# Plant_Monitoring_System.net
KiCad netlist of a schematic drawn in Altium Designer
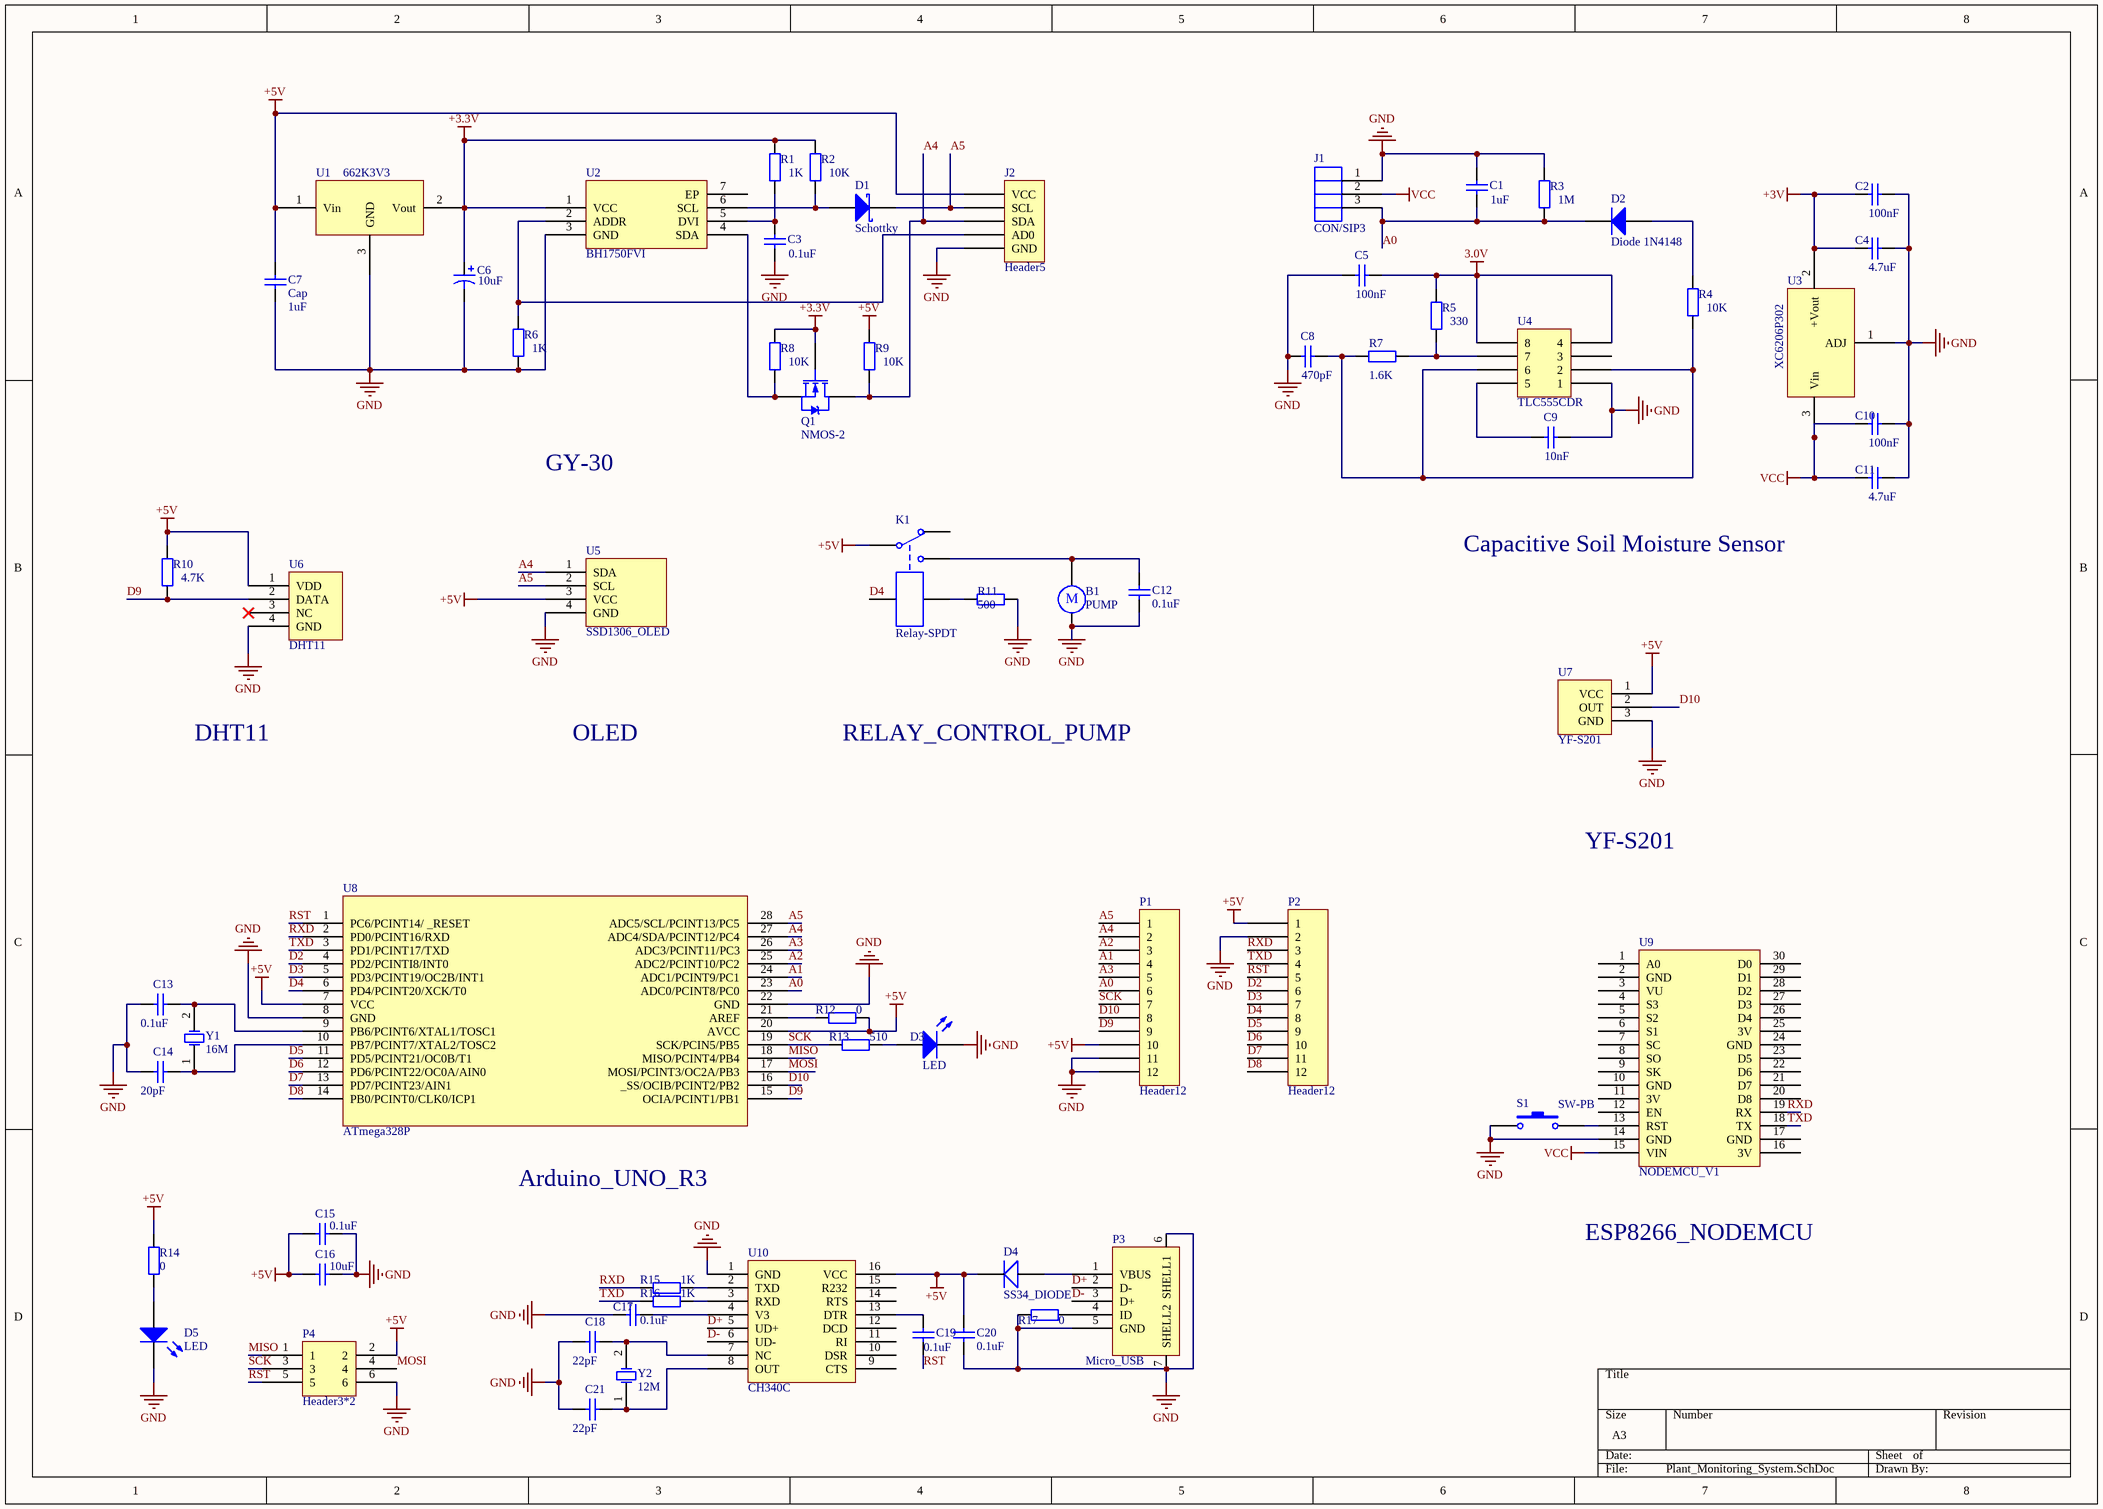
[diagram p0: Plant_Monitoring_System.SchDoc]

(export (version "E")
  (design (tool "Eeschema 10.0.6"))
  (components
    (comp (ref "B1")
      (value "PUMP")
      (footprint "RB5-10.5")
      (description "Motor, General Kind")
      (fields (field (name "PUBLISHER") "Altium Limited"))
      (libsource (lib "Miscellaneous Devices") (part "Motor"))
    )
    (comp (ref "C1")
      (value "1uF")
      (footprint "RAD-0.3")
      (description "Capacitor")
      (fields (field (name "PUBLISHER") "Altium Limited"))
      (libsource (lib "Miscellaneous Devices") (part "Cap"))
    )
    (comp (ref "C2")
      (value "100nF")
      (footprint "RAD-0.3")
      (description "Capacitor")
      (fields (field (name "PUBLISHER") "Altium Limited"))
      (libsource (lib "Miscellaneous Devices") (part "Cap"))
    )
    (comp (ref "C3")
      (value "0.1uF")
      (footprint "RAD-0.3")
      (description "Capacitor")
      (fields (field (name "PUBLISHER") "Altium Limited"))
      (libsource (lib "Miscellaneous Devices") (part "Cap"))
    )
    (comp (ref "C4")
      (value "4.7uF")
      (footprint "RAD-0.3")
      (description "Capacitor")
      (fields (field (name "PUBLISHER") "Altium Limited"))
      (libsource (lib "Miscellaneous Devices") (part "Cap"))
    )
    (comp (ref "C5")
      (value "100nF")
      (footprint "RAD-0.3")
      (description "Capacitor")
      (fields (field (name "PUBLISHER") "Altium Limited"))
      (libsource (lib "Miscellaneous Devices") (part "Cap"))
    )
    (comp (ref "C6")
      (value "10uF")
      (footprint "RB7.6-15")
      (description "Polarized Capacitor (Radial)")
      (fields (field (name "PUBLISHER") "Altium Limited"))
      (libsource (lib "Miscellaneous Devices") (part "Cap Pol1"))
    )
    (comp (ref "C7")
      (value "Cap")
      (footprint "RAD-0.3")
      (description "Capacitor")
      (fields (field (name "ALTIUM_VALUE") "1uF") (field (name "PUBLISHER") "Altium Limited"))
      (libsource (lib "Miscellaneous Devices") (part "Cap"))
    )
    (comp (ref "C8")
      (value "470pF")
      (footprint "RAD-0.3")
      (description "Capacitor")
      (fields (field (name "PUBLISHER") "Altium Limited"))
      (libsource (lib "Miscellaneous Devices") (part "Cap"))
    )
    (comp (ref "C9")
      (value "10nF")
      (footprint "RAD-0.3")
      (description "Capacitor")
      (fields (field (name "PUBLISHER") "Altium Limited"))
      (libsource (lib "Miscellaneous Devices") (part "Cap"))
    )
    (comp (ref "C10")
      (value "100nF")
      (footprint "RAD-0.3")
      (description "Capacitor")
      (fields (field (name "PUBLISHER") "Altium Limited"))
      (libsource (lib "Miscellaneous Devices") (part "Cap"))
    )
    (comp (ref "C11")
      (value "4.7uF")
      (footprint "RAD-0.3")
      (description "Capacitor")
      (fields (field (name "PUBLISHER") "Altium Limited"))
      (libsource (lib "Miscellaneous Devices") (part "Cap"))
    )
    (comp (ref "C12")
      (value "0.1uF")
      (footprint "RAD-0.3")
      (description "Capacitor")
      (fields (field (name "PUBLISHER") "Altium Limited"))
      (libsource (lib "Miscellaneous Devices") (part "Cap"))
    )
    (comp (ref "C13")
      (value "0.1uF")
      (footprint "RAD-0.3")
      (description "Capacitor")
      (fields (field (name "PUBLISHER") "Altium Limited"))
      (libsource (lib "Miscellaneous Devices") (part "Cap"))
    )
    (comp (ref "C14")
      (value "20pF")
      (footprint "RAD-0.3")
      (description "Capacitor")
      (fields (field (name "PUBLISHER") "Altium Limited"))
      (libsource (lib "Miscellaneous Devices") (part "Cap"))
    )
    (comp (ref "C15")
      (value "0.1uF")
      (footprint "RAD-0.3")
      (description "Capacitor")
      (fields (field (name "PUBLISHER") "Altium Limited"))
      (libsource (lib "Miscellaneous Devices") (part "Cap"))
    )
    (comp (ref "C16")
      (value "10uF")
      (footprint "RAD-0.3")
      (description "Capacitor")
      (fields (field (name "PUBLISHER") "Altium Limited"))
      (libsource (lib "Miscellaneous Devices") (part "Cap"))
    )
    (comp (ref "C17")
      (value "0.1uF")
      (footprint "RAD-0.3")
      (description "Capacitor")
      (fields (field (name "PUBLISHER") "Altium Limited"))
      (libsource (lib "Miscellaneous Devices") (part "Cap"))
    )
    (comp (ref "C18")
      (value "22pF")
      (footprint "RAD-0.3")
      (description "Capacitor")
      (fields (field (name "PUBLISHER") "Altium Limited"))
      (libsource (lib "Miscellaneous Devices") (part "Cap"))
    )
    (comp (ref "C19")
      (value "0.1uF")
      (footprint "RAD-0.3")
      (description "Capacitor")
      (fields (field (name "PUBLISHER") "Altium Limited"))
      (libsource (lib "Miscellaneous Devices") (part "Cap"))
    )
    (comp (ref "C20")
      (value "0.1uF")
      (footprint "RAD-0.3")
      (description "Capacitor")
      (fields (field (name "PUBLISHER") "Altium Limited"))
      (libsource (lib "Miscellaneous Devices") (part "Cap"))
    )
    (comp (ref "C21")
      (value "22pF")
      (footprint "RAD-0.3")
      (description "Capacitor")
      (fields (field (name "PUBLISHER") "Altium Limited"))
      (libsource (lib "Miscellaneous Devices") (part "Cap"))
    )
    (comp (ref "D1")
      (value "Schottky")
      (footprint "SMB")
      (description "Schottky Diode")
      (fields (field (name "PUBLISHER") "Altium Limited"))
      (libsource (lib "Miscellaneous Devices") (part "D Schottky"))
    )
    (comp (ref "D2")
      (value "Diode 1N4148")
      (footprint "DO-35")
      (description "High Conductance Fast Diode")
      (fields (field (name "PUBLISHER") "Altium Limited"))
      (libsource (lib "Miscellaneous Devices") (part "Diode 1N4148"))
    )
    (comp (ref "D3")
      (value "LED")
      (footprint "3.5X2.8X1.9")
      (description "Typical BLUE SiC LED")
      (fields (field (name "PUBLISHER") "Altium Limited"))
      (libsource (lib "Miscellaneous Devices") (part "LED3"))
    )
    (comp (ref "D4") (value "SS34_DIODE") (libsource (lib "Arduino") (part "SS34_DIODE")))
    (comp (ref "D5")
      (value "LED")
      (footprint "3.5X2.8X1.9")
      (description "Typical BLUE SiC LED")
      (fields (field (name "PUBLISHER") "Altium Limited"))
      (libsource (lib "Miscellaneous Devices") (part "LED3"))
    )
    (comp (ref "J1") (value "CON/SIP3") (libsource (lib "SOILHUMIDITY") (part "CON/SIP3")))
    (comp (ref "J2") (value "Header5") (libsource (lib "GY-30") (part "Header5")))
    (comp (ref "K1")
      (value "Relay-SPDT")
      (footprint "MODULE5B")
      (description "Single-Pole Dual-Throw Relay")
      (fields (field (name "PUBLISHER") "Altium Limited"))
      (libsource (lib "Miscellaneous Devices") (part "Relay-SPDT"))
    )
    (comp (ref "P1") (value "Header12") (libsource (lib "Arduino") (part "Header12")))
    (comp (ref "P2") (value "Header12") (libsource (lib "Arduino") (part "Header12")))
    (comp (ref "P3") (value "Micro_USB") (libsource (lib "Arduino") (part "Micro_USB")))
    (comp (ref "P4") (value "Header3*2") (libsource (lib "Arduino") (part "Header3*2")))
    (comp (ref "Q1")
      (value "NMOS-2")
      (footprint "TO-220AB")
      (description "N-Channel Power MOSFET")
      (fields (field (name "PUBLISHER") "Altium Limited"))
      (libsource (lib "Miscellaneous Devices") (part "NMOS-2"))
    )
    (comp (ref "R1")
      (value "1K")
      (footprint "AXIAL-0.4")
      (description "Resistor")
      (fields (field (name "PUBLISHER") "Altium Limited"))
      (libsource (lib "") (part "Res2_1"))
    )
    (comp (ref "R2")
      (value "10K")
      (footprint "AXIAL-0.4")
      (description "Resistor")
      (fields (field (name "PUBLISHER") "Altium Limited"))
      (libsource (lib "") (part "Res2_1"))
    )
    (comp (ref "R3")
      (value "1M")
      (footprint "AXIAL-0.4")
      (description "Resistor")
      (fields (field (name "PUBLISHER") "Altium Limited"))
      (libsource (lib "") (part "Res2_1"))
    )
    (comp (ref "R4")
      (value "10K")
      (footprint "AXIAL-0.4")
      (description "Resistor")
      (fields (field (name "PUBLISHER") "Altium Limited"))
      (libsource (lib "") (part "Res2_1"))
    )
    (comp (ref "R5")
      (value "330")
      (footprint "AXIAL-0.4")
      (description "Resistor")
      (fields (field (name "PUBLISHER") "Altium Limited"))
      (libsource (lib "") (part "Res2_1"))
    )
    (comp (ref "R6")
      (value "1K")
      (footprint "AXIAL-0.4")
      (description "Resistor")
      (fields (field (name "PUBLISHER") "Altium Limited"))
      (libsource (lib "") (part "Res2_1"))
    )
    (comp (ref "R7")
      (value "1.6K")
      (footprint "AXIAL-0.4")
      (description "Resistor")
      (fields (field (name "PUBLISHER") "Altium Limited"))
      (libsource (lib "Miscellaneous Devices") (part "Res2"))
    )
    (comp (ref "R8")
      (value "10K")
      (footprint "AXIAL-0.4")
      (description "Resistor")
      (fields (field (name "PUBLISHER") "Altium Limited"))
      (libsource (lib "") (part "Res2_1"))
    )
    (comp (ref "R9")
      (value "10K")
      (footprint "AXIAL-0.4")
      (description "Resistor")
      (fields (field (name "PUBLISHER") "Altium Limited"))
      (libsource (lib "") (part "Res2_1"))
    )
    (comp (ref "R10")
      (value "4.7K")
      (footprint "AXIAL-0.4")
      (description "Resistor")
      (fields (field (name "PUBLISHER") "Altium Limited"))
      (libsource (lib "") (part "Res2_1"))
    )
    (comp (ref "R11")
      (value "500")
      (footprint "AXIAL-0.4")
      (description "Resistor")
      (fields (field (name "PUBLISHER") "Altium Limited"))
      (libsource (lib "Miscellaneous Devices") (part "Res2"))
    )
    (comp (ref "R12")
      (value "0")
      (footprint "AXIAL-0.4")
      (description "Resistor")
      (fields (field (name "PUBLISHER") "Altium Limited"))
      (libsource (lib "Miscellaneous Devices") (part "Res2"))
    )
    (comp (ref "R13")
      (value "510")
      (footprint "AXIAL-0.4")
      (description "Resistor")
      (fields (field (name "PUBLISHER") "Altium Limited"))
      (libsource (lib "Miscellaneous Devices") (part "Res2"))
    )
    (comp (ref "R14")
      (value "0")
      (footprint "AXIAL-0.4")
      (description "Resistor")
      (fields (field (name "PUBLISHER") "Altium Limited"))
      (libsource (lib "") (part "Res2_2"))
    )
    (comp (ref "R15")
      (value "1K")
      (footprint "AXIAL-0.4")
      (description "Resistor")
      (fields (field (name "PUBLISHER") "Altium Limited"))
      (libsource (lib "Miscellaneous Devices") (part "Res2"))
    )
    (comp (ref "R16")
      (value "1K")
      (footprint "AXIAL-0.4")
      (description "Resistor")
      (fields (field (name "PUBLISHER") "Altium Limited"))
      (libsource (lib "Miscellaneous Devices") (part "Res2"))
    )
    (comp (ref "R17")
      (value "0")
      (footprint "AXIAL-0.4")
      (description "Resistor")
      (fields (field (name "PUBLISHER") "Altium Limited"))
      (libsource (lib "Miscellaneous Devices") (part "Res2"))
    )
    (comp (ref "S1")
      (value "SW-PB")
      (footprint "SPST-2")
      (description "Switch")
      (fields (field (name "PUBLISHER") "Altium Limited"))
      (libsource (lib "Miscellaneous Devices") (part "SW-PB"))
    )
    (comp (ref "U1") (value "662K3V3") (libsource (lib "GY-30") (part "662K3V3")))
    (comp (ref "U2") (value "BH1750FVI") (libsource (lib "GY-30") (part "BH1750FVI")))
    (comp (ref "U3") (value "XC6206P302") (libsource (lib "SOILHUMIDITY") (part "XC6206P302")))
    (comp (ref "U4") (value "TLC555CDR") (libsource (lib "SOILHUMIDITY") (part "TLC555CDR")))
    (comp (ref "U5") (value "SSD1306_OLED") (libsource (lib "OLEDIIC128X64") (part "SSD1306_OLED")))
    (comp (ref "U6") (value "DHT11") (libsource (lib "DHT11") (part "DHT11")))
    (comp (ref "U7") (value "YF-S201") (libsource (lib "YF-S201") (part "YF-S201")))
    (comp (ref "U8") (value "ATmega328P") (libsource (lib "Arduino") (part "ATmega328P")))
    (comp (ref "U9") (value "NODEMCU_V1") (libsource (lib "ESP8266") (part "NODEMCU_V1")))
    (comp (ref "U10") (value "CH340C") (libsource (lib "Arduino") (part "CH340C")))
    (comp (ref "Y1")
      (value "16M")
      (footprint "R38")
      (description "Crystal Oscillator")
      (fields (field (name "PUBLISHER") "Altium Limited"))
      (libsource (lib "Miscellaneous Devices") (part "XTAL"))
    )
    (comp (ref "Y2")
      (value "12M")
      (footprint "R38")
      (description "Crystal Oscillator")
      (fields (field (name "PUBLISHER") "Altium Limited"))
      (libsource (lib "Miscellaneous Devices") (part "XTAL"))
    )
  )
  (nets
    (net (code "1") (name "+3.3V") (class "Default")
      (node (ref "C6") (pin "1") (pinfunction "1_1") (pintype "passive"))
      (node (ref "Q1") (pin "1") (pinfunction "G_1") (pintype "passive"))
      (node (ref "R1") (pin "2") (pinfunction "2_2") (pintype "passive"))
      (node (ref "R2") (pin "2") (pinfunction "2_2") (pintype "passive"))
      (node (ref "R8") (pin "2") (pinfunction "2_2") (pintype "passive"))
      (node (ref "U1") (pin "2") (pinfunction "Vout_2") (pintype "passive"))
      (node (ref "U2") (pin "1") (pinfunction "VCC_1") (pintype "passive"))
    )
    (net (code "2") (name "+3V") (class "Default")
      (node (ref "C2") (pin "1") (pinfunction "1_1") (pintype "passive"))
      (node (ref "C4") (pin "1") (pinfunction "1_1") (pintype "passive"))
      (node (ref "U3") (pin "2") (pinfunction "+Vout_2") (pintype "passive"))
    )
    (net (code "3") (name "+5V") (class "Default")
      (node (ref "C15") (pin "1") (pinfunction "1_1") (pintype "passive"))
      (node (ref "C16") (pin "2") (pinfunction "2_2") (pintype "passive"))
      (node (ref "C20") (pin "1") (pinfunction "1_1") (pintype "passive"))
      (node (ref "C7") (pin "2") (pinfunction "2_2") (pintype "passive"))
      (node (ref "J2") (pin "1") (pinfunction "VCC_1") (pintype "passive"))
      (node (ref "K1") (pin "1") (pinfunction "1_1") (pintype "passive"))
      (node (ref "P1") (pin "10") (pinfunction "10_10") (pintype "passive"))
      (node (ref "P2") (pin "1") (pinfunction "1_1") (pintype "passive"))
      (node (ref "P4") (pin "2") (pinfunction "2_2") (pintype "passive"))
      (node (ref "R10") (pin "2") (pinfunction "2_2") (pintype "passive"))
      (node (ref "R12") (pin "2") (pinfunction "2_2") (pintype "passive"))
      (node (ref "R14") (pin "1") (pinfunction "1_1") (pintype "passive"))
      (node (ref "R9") (pin "2") (pinfunction "2_2") (pintype "passive"))
      (node (ref "U1") (pin "1") (pinfunction "Vin_1") (pintype "passive"))
      (node (ref "U10") (pin "16") (pinfunction "VCC_16") (pintype "passive"))
      (node (ref "U5") (pin "3") (pinfunction "VCC_3") (pintype "passive"))
      (node (ref "U6") (pin "1") (pinfunction "VDD_1") (pintype "passive"))
      (node (ref "U7") (pin "1") (pinfunction "VCC_1") (pintype "passive"))
      (node (ref "U8") (pin "20") (pinfunction "AVCC_20") (pintype "passive"))
      (node (ref "U8") (pin "7") (pinfunction "VCC_7") (pintype "passive"))
    )
    (net (code "4") (name "/A0") (class "Default")
      (node (ref "C1") (pin "1") (pinfunction "1_1") (pintype "passive"))
      (node (ref "D2") (pin "2") (pinfunction "K_2") (pintype "passive"))
      (node (ref "J1") (pin "3") (pinfunction "3_3") (pintype "passive"))
      (node (ref "P1") (pin "6") (pinfunction "6_6") (pintype "passive"))
      (node (ref "R3") (pin "1") (pinfunction "1_1") (pintype "passive"))
      (node (ref "U8") (pin "23") (pinfunction "ADC0/PCINT8/PC0_23") (pintype "passive"))
    )
    (net (code "5") (name "/A1") (class "Default")
      (node (ref "P1") (pin "4") (pinfunction "4_4") (pintype "passive"))
      (node (ref "U8") (pin "24") (pinfunction "ADC1/PCINT9/PC1_24") (pintype "passive"))
    )
    (net (code "6") (name "/A2") (class "Default")
      (node (ref "P1") (pin "3") (pinfunction "3_3") (pintype "passive"))
      (node (ref "U8") (pin "25") (pinfunction "ADC2/PCINT10/PC2_25") (pintype "passive"))
    )
    (net (code "7") (name "/A3") (class "Default")
      (node (ref "P1") (pin "5") (pinfunction "5_5") (pintype "passive"))
      (node (ref "U8") (pin "26") (pinfunction "ADC3/PCINT11/PC3_26") (pintype "passive"))
    )
    (net (code "8") (name "/A4") (class "Default")
      (node (ref "J2") (pin "3") (pinfunction "SDA_3") (pintype "passive"))
      (node (ref "P1") (pin "2") (pinfunction "2_2") (pintype "passive"))
      (node (ref "Q1") (pin "2") (pinfunction "D_2") (pintype "passive"))
      (node (ref "R9") (pin "1") (pinfunction "1_1") (pintype "passive"))
      (node (ref "U5") (pin "1") (pinfunction "SDA_1") (pintype "passive"))
      (node (ref "U8") (pin "27") (pinfunction "ADC4/SDA/PCINT12/PC4_27") (pintype "passive"))
    )
    (net (code "9") (name "/A5") (class "Default")
      (node (ref "D1") (pin "2") (pinfunction "K_2") (pintype "passive"))
      (node (ref "J2") (pin "2") (pinfunction "SCL_2") (pintype "passive"))
      (node (ref "P1") (pin "1") (pinfunction "1_1") (pintype "passive"))
      (node (ref "U5") (pin "2") (pinfunction "SCL_2") (pintype "passive"))
      (node (ref "U8") (pin "28") (pinfunction "ADC5/SCL/PCINT13/PC5_28") (pintype "passive"))
    )
    (net (code "10") (name "/D+") (class "Default")
      (node (ref "P3") (pin "2") (pinfunction "D-_2") (pintype "passive"))
      (node (ref "U10") (pin "5") (pinfunction "UD+_5") (pintype "passive"))
    )
    (net (code "11") (name "/D-") (class "Default")
      (node (ref "P3") (pin "3") (pinfunction "D+_3") (pintype "passive"))
      (node (ref "U10") (pin "6") (pinfunction "UD-_6") (pintype "passive"))
    )
    (net (code "12") (name "/D2") (class "Default")
      (node (ref "P2") (pin "6") (pinfunction "6_6") (pintype "passive"))
      (node (ref "U8") (pin "4") (pinfunction "PD2/PCINTI8/INT0_4") (pintype "passive"))
    )
    (net (code "13") (name "/D3") (class "Default")
      (node (ref "P2") (pin "7") (pinfunction "7_7") (pintype "passive"))
      (node (ref "U8") (pin "5") (pinfunction "PD3/PCINT19/OC2B/INT1_5") (pintype "passive"))
    )
    (net (code "14") (name "/D4") (class "Default")
      (node (ref "K1") (pin "4") (pinfunction "4_4") (pintype "passive"))
      (node (ref "P2") (pin "8") (pinfunction "8_8") (pintype "passive"))
      (node (ref "U8") (pin "6") (pinfunction "PD4/PCINT20/XCK/T0_6") (pintype "passive"))
    )
    (net (code "15") (name "/D5") (class "Default")
      (node (ref "P2") (pin "9") (pinfunction "9_9") (pintype "passive"))
      (node (ref "U8") (pin "11") (pinfunction "PD5/PCINT21/OC0B/T1_11") (pintype "passive"))
    )
    (net (code "16") (name "/D6") (class "Default")
      (node (ref "P2") (pin "10") (pinfunction "10_10") (pintype "passive"))
      (node (ref "U8") (pin "12") (pinfunction "PD6/PCINT22/OC0A/AIN0_12") (pintype "passive"))
    )
    (net (code "17") (name "/D7") (class "Default")
      (node (ref "P2") (pin "11") (pinfunction "11_11") (pintype "passive"))
      (node (ref "U8") (pin "13") (pinfunction "PD7/PCINT23/AIN1_13") (pintype "passive"))
    )
    (net (code "18") (name "/D8") (class "Default")
      (node (ref "P2") (pin "12") (pinfunction "12_12") (pintype "passive"))
      (node (ref "U8") (pin "14") (pinfunction "PB0/PCINT0/CLK0/ICP1_14") (pintype "passive"))
    )
    (net (code "19") (name "/D9") (class "Default")
      (node (ref "P1") (pin "9") (pinfunction "9_9") (pintype "passive"))
      (node (ref "R10") (pin "1") (pinfunction "1_1") (pintype "passive"))
      (node (ref "U6") (pin "2") (pinfunction "DATA_2") (pintype "passive"))
      (node (ref "U8") (pin "15") (pinfunction "OCIA/PCINT1/PB1_15") (pintype "passive"))
    )
    (net (code "20") (name "/D10") (class "Default")
      (node (ref "P1") (pin "8") (pinfunction "8_8") (pintype "passive"))
      (node (ref "U7") (pin "2") (pinfunction "OUT_2") (pintype "passive"))
      (node (ref "U8") (pin "16") (pinfunction "_SS/OCIB/PCINT2/PB2_16") (pintype "passive"))
    )
    (net (code "21") (name "/MISO") (class "Default")
      (node (ref "P4") (pin "1") (pinfunction "1_1") (pintype "passive"))
      (node (ref "U8") (pin "18") (pinfunction "MISO/PCINT4/PB4_18") (pintype "passive"))
    )
    (net (code "22") (name "/MOSI") (class "Default")
      (node (ref "P4") (pin "4") (pinfunction "4_4") (pintype "passive"))
      (node (ref "U8") (pin "17") (pinfunction "MOSI/PCINT3/OC2A/PB3_17") (pintype "passive"))
    )
    (net (code "23") (name "/RST") (class "Default")
      (node (ref "C19") (pin "1") (pinfunction "1_1") (pintype "passive"))
      (node (ref "P2") (pin "5") (pinfunction "5_5") (pintype "passive"))
      (node (ref "P4") (pin "5") (pinfunction "5_5") (pintype "passive"))
      (node (ref "U8") (pin "1") (pinfunction "PC6/PCINT14/__RESET_1") (pintype "passive"))
    )
    (net (code "24") (name "/RXD") (class "Default")
      (node (ref "P2") (pin "3") (pinfunction "3_3") (pintype "passive"))
      (node (ref "R15") (pin "1") (pinfunction "1_1") (pintype "passive"))
      (node (ref "U8") (pin "2") (pinfunction "PD0/PCINT16/RXD_2") (pintype "passive"))
      (node (ref "U9") (pin "19") (pinfunction "RX_19") (pintype "passive"))
    )
    (net (code "25") (name "/SCK") (class "Default")
      (node (ref "P1") (pin "7") (pinfunction "7_7") (pintype "passive"))
      (node (ref "P4") (pin "3") (pinfunction "3_3") (pintype "passive"))
      (node (ref "R13") (pin "1") (pinfunction "1_1") (pintype "passive"))
      (node (ref "U8") (pin "19") (pinfunction "SCK/PCIN5/PB5_19") (pintype "passive"))
    )
    (net (code "26") (name "/TXD") (class "Default")
      (node (ref "P2") (pin "4") (pinfunction "4_4") (pintype "passive"))
      (node (ref "R16") (pin "1") (pinfunction "1_1") (pintype "passive"))
      (node (ref "U8") (pin "3") (pinfunction "PD1/PCINT17/TXD_3") (pintype "passive"))
      (node (ref "U9") (pin "18") (pinfunction "TX_18") (pintype "passive"))
    )
    (net (code "27") (name "3.0V") (class "Default")
      (node (ref "C5") (pin "2") (pinfunction "2_2") (pintype "passive"))
      (node (ref "R5") (pin "2") (pinfunction "2_2") (pintype "passive"))
      (node (ref "U4") (pin "4") (pinfunction "4_4") (pintype "passive"))
      (node (ref "U4") (pin "8") (pinfunction "8_8") (pintype "passive"))
    )
    (net (code "28") (name "GND") (class "Default")
      (node (ref "B1") (pin "2") (pinfunction "2_2") (pintype "passive"))
      (node (ref "C1") (pin "2") (pinfunction "2_2") (pintype "passive"))
      (node (ref "C10") (pin "2") (pinfunction "2_2") (pintype "passive"))
      (node (ref "C11") (pin "2") (pinfunction "2_2") (pintype "passive"))
      (node (ref "C12") (pin "2") (pinfunction "2_2") (pintype "passive"))
      (node (ref "C13") (pin "2") (pinfunction "2_2") (pintype "passive"))
      (node (ref "C14") (pin "2") (pinfunction "2_2") (pintype "passive"))
      (node (ref "C15") (pin "2") (pinfunction "2_2") (pintype "passive"))
      (node (ref "C16") (pin "1") (pinfunction "1_1") (pintype "passive"))
      (node (ref "C17") (pin "2") (pinfunction "2_2") (pintype "passive"))
      (node (ref "C18") (pin "2") (pinfunction "2_2") (pintype "passive"))
      (node (ref "C2") (pin "2") (pinfunction "2_2") (pintype "passive"))
      (node (ref "C20") (pin "2") (pinfunction "2_2") (pintype "passive"))
      (node (ref "C21") (pin "2") (pinfunction "2_2") (pintype "passive"))
      (node (ref "C3") (pin "1") (pinfunction "1_1") (pintype "passive"))
      (node (ref "C4") (pin "2") (pinfunction "2_2") (pintype "passive"))
      (node (ref "C5") (pin "1") (pinfunction "1_1") (pintype "passive"))
      (node (ref "C6") (pin "2") (pinfunction "2_2") (pintype "passive"))
      (node (ref "C7") (pin "1") (pinfunction "1_1") (pintype "passive"))
      (node (ref "C8") (pin "1") (pinfunction "1_1") (pintype "passive"))
      (node (ref "C9") (pin "2") (pinfunction "2_2") (pintype "passive"))
      (node (ref "D3") (pin "2") (pinfunction "K_2") (pintype "passive"))
      (node (ref "D5") (pin "2") (pinfunction "K_2") (pintype "passive"))
      (node (ref "J1") (pin "1") (pinfunction "1_1") (pintype "passive"))
      (node (ref "J2") (pin "5") (pinfunction "GND_5") (pintype "passive"))
      (node (ref "P1") (pin "11") (pinfunction "11_11") (pintype "passive"))
      (node (ref "P1") (pin "12") (pinfunction "12_12") (pintype "passive"))
      (node (ref "P2") (pin "2") (pinfunction "2_2") (pintype "passive"))
      (node (ref "P3") (pin "5") (pinfunction "GND_5") (pintype "passive"))
      (node (ref "P3") (pin "6") (pinfunction "SHELL1_6") (pintype "passive"))
      (node (ref "P3") (pin "7") (pinfunction "SHELL2_7") (pintype "passive"))
      (node (ref "P4") (pin "6") (pinfunction "6_6") (pintype "passive"))
      (node (ref "R11") (pin "2") (pinfunction "2_2") (pintype "passive"))
      (node (ref "R17") (pin "1") (pinfunction "1_1") (pintype "passive"))
      (node (ref "R3") (pin "2") (pinfunction "2_2") (pintype "passive"))
      (node (ref "R6") (pin "1") (pinfunction "1_1") (pintype "passive"))
      (node (ref "S1") (pin "1") (pinfunction "1_1") (pintype "passive"))
      (node (ref "U1") (pin "3") (pinfunction "GND_3") (pintype "passive"))
      (node (ref "U10") (pin "1") (pinfunction "GND_1") (pintype "passive"))
      (node (ref "U2") (pin "3") (pinfunction "GND_3") (pintype "passive"))
      (node (ref "U3") (pin "1") (pinfunction "ADJ_1") (pintype "passive"))
      (node (ref "U4") (pin "1") (pinfunction "1_1") (pintype "passive"))
      (node (ref "U5") (pin "4") (pinfunction "GND_4") (pintype "passive"))
      (node (ref "U6") (pin "4") (pinfunction "GND_4") (pintype "passive"))
      (node (ref "U7") (pin "3") (pinfunction "GND_3") (pintype "passive"))
      (node (ref "U8") (pin "22") (pinfunction "GND_22") (pintype "passive"))
      (node (ref "U8") (pin "8") (pinfunction "GND_8") (pintype "passive"))
      (node (ref "U9") (pin "14") (pinfunction "GND_14") (pintype "passive"))
    )
    (net (code "29") (name "Net-(B1-Pad1)") (class "Default")
      (node (ref "B1") (pin "1") (pinfunction "1_1") (pintype "passive"))
      (node (ref "C12") (pin "1") (pinfunction "1_1") (pintype "passive"))
      (node (ref "K1") (pin "3") (pinfunction "3_3") (pintype "passive"))
    )
    (net (code "30") (name "Net-(C8-Pad2)") (class "Default")
      (node (ref "C8") (pin "2") (pinfunction "2_2") (pintype "passive"))
      (node (ref "R4") (pin "1") (pinfunction "1_1") (pintype "passive"))
      (node (ref "R7") (pin "1") (pinfunction "1_1") (pintype "passive"))
      (node (ref "U4") (pin "2") (pinfunction "2_2") (pintype "passive"))
      (node (ref "U4") (pin "6") (pinfunction "6_6") (pintype "passive"))
    )
    (net (code "31") (name "Net-(C9-Pad1)") (class "Default")
      (node (ref "C9") (pin "1") (pinfunction "1_1") (pintype "passive"))
      (node (ref "U4") (pin "5") (pinfunction "5_5") (pintype "passive"))
    )
    (net (code "32") (name "Net-(D1-A)") (class "Default")
      (node (ref "D1") (pin "1") (pinfunction "A_1") (pintype "passive"))
      (node (ref "R2") (pin "1") (pinfunction "1_1") (pintype "passive"))
      (node (ref "U2") (pin "6") (pinfunction "SCL_6") (pintype "passive"))
    )
    (net (code "33") (name "Net-(D2-A)") (class "Default")
      (node (ref "D2") (pin "1") (pinfunction "A_1") (pintype "passive"))
      (node (ref "R4") (pin "2") (pinfunction "2_2") (pintype "passive"))
    )
    (net (code "34") (name "Net-(D3-A)") (class "Default")
      (node (ref "D3") (pin "1") (pinfunction "A_1") (pintype "passive"))
      (node (ref "R13") (pin "2") (pinfunction "2_2") (pintype "passive"))
    )
    (net (code "35") (name "Net-(D5-A)") (class "Default")
      (node (ref "D5") (pin "1") (pinfunction "A_1") (pintype "passive"))
      (node (ref "R14") (pin "2") (pinfunction "2_2") (pintype "passive"))
    )
    (net (code "36") (name "Net-(J2-AD0)") (class "Default")
      (node (ref "J2") (pin "4") (pinfunction "AD0_4") (pintype "passive"))
      (node (ref "R6") (pin "2") (pinfunction "2_2") (pintype "passive"))
      (node (ref "U2") (pin "2") (pinfunction "ADDR_2") (pintype "passive"))
    )
    (net (code "37") (name "Net-(K1-Pad5)") (class "Default")
      (node (ref "K1") (pin "5") (pinfunction "5_5") (pintype "passive"))
      (node (ref "R11") (pin "1") (pinfunction "1_1") (pintype "passive"))
    )
    (net (code "38") (name "Net-(P3-ID)") (class "Default")
      (node (ref "P3") (pin "4") (pinfunction "ID_4") (pintype "passive"))
      (node (ref "R17") (pin "2") (pinfunction "2_2") (pintype "passive"))
    )
    (net (code "39") (name "Net-(Q1-S)") (class "Default")
      (node (ref "Q1") (pin "3") (pinfunction "S_3") (pintype "passive"))
      (node (ref "R8") (pin "1") (pinfunction "1_1") (pintype "passive"))
      (node (ref "U2") (pin "4") (pinfunction "SDA_4") (pintype "passive"))
    )
    (net (code "40") (name "Net-(R5-Pad1)") (class "Default")
      (node (ref "R5") (pin "1") (pinfunction "1_1") (pintype "passive"))
      (node (ref "R7") (pin "2") (pinfunction "2_2") (pintype "passive"))
      (node (ref "U4") (pin "7") (pinfunction "7_7") (pintype "passive"))
    )
    (net (code "41") (name "Net-(U2-DVI)") (class "Default")
      (node (ref "C3") (pin "2") (pinfunction "2_2") (pintype "passive"))
      (node (ref "R1") (pin "1") (pinfunction "1_1") (pintype "passive"))
      (node (ref "U2") (pin "5") (pinfunction "DVI_5") (pintype "passive"))
    )
    (net (code "42") (name "Net-(U8-AREF)") (class "Default")
      (node (ref "R12") (pin "1") (pinfunction "1_1") (pintype "passive"))
      (node (ref "U8") (pin "21") (pinfunction "AREF_21") (pintype "passive"))
    )
    (net (code "43") (name "Net-(U8-PB6{slash}PCINT6{slash}XTAL1{slash}TOSC1)") (class "Default")
      (node (ref "C13") (pin "1") (pinfunction "1_1") (pintype "passive"))
      (node (ref "U8") (pin "9") (pinfunction "PB6/PCINT6/XTAL1/TOSC1_9") (pintype "passive"))
      (node (ref "Y1") (pin "2") (pinfunction "OSC2_2") (pintype "passive"))
    )
    (net (code "44") (name "Net-(U8-PB7{slash}PCINT7{slash}XTAL2{slash}TOSC2)") (class "Default")
      (node (ref "C14") (pin "1") (pinfunction "1_1") (pintype "passive"))
      (node (ref "U8") (pin "10") (pinfunction "PB7/PCINT7/XTAL2/TOSC2_10") (pintype "passive"))
      (node (ref "Y1") (pin "1") (pinfunction "OSC1_1") (pintype "passive"))
    )
    (net (code "45") (name "Net-(U9-RST)") (class "Default")
      (node (ref "S1") (pin "2") (pinfunction "2_2") (pintype "passive"))
      (node (ref "U9") (pin "13") (pinfunction "RST_13") (pintype "passive"))
    )
    (net (code "46") (name "Net-(U10-DTR)") (class "Default")
      (node (ref "C19") (pin "2") (pinfunction "2_2") (pintype "passive"))
      (node (ref "U10") (pin "13") (pinfunction "DTR_13") (pintype "passive"))
    )
    (net (code "47") (name "Net-(U10-NC)") (class "Default")
      (node (ref "C18") (pin "1") (pinfunction "1_1") (pintype "passive"))
      (node (ref "U10") (pin "7") (pinfunction "NC_7") (pintype "passive"))
      (node (ref "Y2") (pin "2") (pinfunction "OSC2_2") (pintype "passive"))
    )
    (net (code "48") (name "Net-(U10-OUT)") (class "Default")
      (node (ref "C21") (pin "1") (pinfunction "1_1") (pintype "passive"))
      (node (ref "U10") (pin "8") (pinfunction "OUT_8") (pintype "passive"))
      (node (ref "Y2") (pin "1") (pinfunction "OSC1_1") (pintype "passive"))
    )
    (net (code "49") (name "Net-(U10-RXD)") (class "Default")
      (node (ref "R16") (pin "2") (pinfunction "2_2") (pintype "passive"))
      (node (ref "U10") (pin "3") (pinfunction "RXD_3") (pintype "passive"))
    )
    (net (code "50") (name "Net-(U10-TXD)") (class "Default")
      (node (ref "R15") (pin "2") (pinfunction "2_2") (pintype "passive"))
      (node (ref "U10") (pin "2") (pinfunction "TXD_2") (pintype "passive"))
    )
    (net (code "51") (name "Net-(U10-V3)") (class "Default")
      (node (ref "C17") (pin "1") (pinfunction "1_1") (pintype "passive"))
      (node (ref "U10") (pin "4") (pinfunction "V3_4") (pintype "passive"))
    )
    (net (code "52") (name "VCC") (class "Default")
      (node (ref "C10") (pin "1") (pinfunction "1_1") (pintype "passive"))
      (node (ref "C11") (pin "1") (pinfunction "1_1") (pintype "passive"))
      (node (ref "J1") (pin "2") (pinfunction "2_2") (pintype "passive"))
      (node (ref "U3") (pin "3") (pinfunction "Vin_3") (pintype "passive"))
      (node (ref "U9") (pin "15") (pinfunction "VIN_15") (pintype "passive"))
    )
    (net (code "53") (name "unconnected-(D4-Pad)") (class "Default")
      (node (ref "D4") (pin "") (pintype "passive"))
    )
    (net (code "54") (name "unconnected-(D4-Pad)_1") (class "Default")
      (node (ref "D4") (pin "") (pintype "passive"))
    )
    (net (code "55") (name "unconnected-(K1-Pad2)") (class "Default")
      (node (ref "K1") (pin "2") (pinfunction "2_2") (pintype "passive"))
    )
    (net (code "56") (name "unconnected-(P3-VBUS-Pad1)") (class "Default")
      (node (ref "P3") (pin "1") (pinfunction "VBUS_1") (pintype "passive"))
    )
    (net (code "57") (name "unconnected-(U2-EP-Pad7)") (class "Default")
      (node (ref "U2") (pin "7") (pinfunction "EP_7") (pintype "passive"))
    )
    (net (code "58") (name "unconnected-(U4-Pad3)") (class "Default")
      (node (ref "U4") (pin "3") (pinfunction "3_3") (pintype "passive"))
    )
    (net (code "59") (name "unconnected-(U6-NC-Pad3)") (class "Default")
      (node (ref "U6") (pin "3") (pinfunction "NC_3") (pintype "passive+no_connect"))
    )
    (net (code "60") (name "unconnected-(U9-3V-Pad11)") (class "Default")
      (node (ref "U9") (pin "11") (pinfunction "3V_11") (pintype "passive"))
    )
    (net (code "61") (name "unconnected-(U9-3V-Pad16)") (class "Default")
      (node (ref "U9") (pin "16") (pinfunction "3V_16") (pintype "passive"))
    )
    (net (code "62") (name "unconnected-(U9-3V-Pad25)") (class "Default")
      (node (ref "U9") (pin "25") (pinfunction "3V_25") (pintype "passive"))
    )
    (net (code "63") (name "unconnected-(U9-A0-Pad1)") (class "Default")
      (node (ref "U9") (pin "1") (pinfunction "A0_1") (pintype "passive"))
    )
    (net (code "64") (name "unconnected-(U9-D0-Pad30)") (class "Default")
      (node (ref "U9") (pin "30") (pinfunction "D0_30") (pintype "passive"))
    )
    (net (code "65") (name "unconnected-(U9-D1-Pad29)") (class "Default")
      (node (ref "U9") (pin "29") (pinfunction "D1_29") (pintype "passive"))
    )
    (net (code "66") (name "unconnected-(U9-D2-Pad28)") (class "Default")
      (node (ref "U9") (pin "28") (pinfunction "D2_28") (pintype "passive"))
    )
    (net (code "67") (name "unconnected-(U9-D3-Pad27)") (class "Default")
      (node (ref "U9") (pin "27") (pinfunction "D3_27") (pintype "passive"))
    )
    (net (code "68") (name "unconnected-(U9-D4-Pad26)") (class "Default")
      (node (ref "U9") (pin "26") (pinfunction "D4_26") (pintype "passive"))
    )
    (net (code "69") (name "unconnected-(U9-D5-Pad23)") (class "Default")
      (node (ref "U9") (pin "23") (pinfunction "D5_23") (pintype "passive"))
    )
    (net (code "70") (name "unconnected-(U9-D6-Pad22)") (class "Default")
      (node (ref "U9") (pin "22") (pinfunction "D6_22") (pintype "passive"))
    )
    (net (code "71") (name "unconnected-(U9-D7-Pad21)") (class "Default")
      (node (ref "U9") (pin "21") (pinfunction "D7_21") (pintype "passive"))
    )
    (net (code "72") (name "unconnected-(U9-D8-Pad20)") (class "Default")
      (node (ref "U9") (pin "20") (pinfunction "D8_20") (pintype "passive"))
    )
    (net (code "73") (name "unconnected-(U9-EN-Pad12)") (class "Default")
      (node (ref "U9") (pin "12") (pinfunction "EN_12") (pintype "passive"))
    )
    (net (code "74") (name "unconnected-(U9-GND-Pad2)") (class "Default")
      (node (ref "U9") (pin "2") (pinfunction "GND_2") (pintype "passive"))
    )
    (net (code "75") (name "unconnected-(U9-GND-Pad10)") (class "Default")
      (node (ref "U9") (pin "10") (pinfunction "GND_10") (pintype "passive"))
    )
    (net (code "76") (name "unconnected-(U9-GND-Pad17)") (class "Default")
      (node (ref "U9") (pin "17") (pinfunction "GND_17") (pintype "passive"))
    )
    (net (code "77") (name "unconnected-(U9-GND-Pad24)") (class "Default")
      (node (ref "U9") (pin "24") (pinfunction "GND_24") (pintype "passive"))
    )
    (net (code "78") (name "unconnected-(U9-S1-Pad6)") (class "Default")
      (node (ref "U9") (pin "6") (pinfunction "S1_6") (pintype "passive"))
    )
    (net (code "79") (name "unconnected-(U9-S2-Pad5)") (class "Default")
      (node (ref "U9") (pin "5") (pinfunction "S2_5") (pintype "passive"))
    )
    (net (code "80") (name "unconnected-(U9-S3-Pad4)") (class "Default")
      (node (ref "U9") (pin "4") (pinfunction "S3_4") (pintype "passive"))
    )
    (net (code "81") (name "unconnected-(U9-SC-Pad7)") (class "Default")
      (node (ref "U9") (pin "7") (pinfunction "SC_7") (pintype "passive"))
    )
    (net (code "82") (name "unconnected-(U9-SK-Pad9)") (class "Default")
      (node (ref "U9") (pin "9") (pinfunction "SK_9") (pintype "passive"))
    )
    (net (code "83") (name "unconnected-(U9-SO-Pad8)") (class "Default")
      (node (ref "U9") (pin "8") (pinfunction "SO_8") (pintype "passive"))
    )
    (net (code "84") (name "unconnected-(U9-VU-Pad3)") (class "Default")
      (node (ref "U9") (pin "3") (pinfunction "VU_3") (pintype "passive"))
    )
    (net (code "85") (name "unconnected-(U10-CTS-Pad9)") (class "Default")
      (node (ref "U10") (pin "9") (pinfunction "CTS_9") (pintype "passive"))
    )
    (net (code "86") (name "unconnected-(U10-DCD-Pad12)") (class "Default")
      (node (ref "U10") (pin "12") (pinfunction "DCD_12") (pintype "passive"))
    )
    (net (code "87") (name "unconnected-(U10-DSR-Pad10)") (class "Default")
      (node (ref "U10") (pin "10") (pinfunction "DSR_10") (pintype "passive"))
    )
    (net (code "88") (name "unconnected-(U10-R232-Pad15)") (class "Default")
      (node (ref "U10") (pin "15") (pinfunction "R232_15") (pintype "passive"))
    )
    (net (code "89") (name "unconnected-(U10-RI-Pad11)") (class "Default")
      (node (ref "U10") (pin "11") (pinfunction "RI_11") (pintype "passive"))
    )
    (net (code "90") (name "unconnected-(U10-RTS-Pad14)") (class "Default")
      (node (ref "U10") (pin "14") (pinfunction "RTS_14") (pintype "passive"))
    )
  )
)
